# mcu.net
KiCad netlist of a schematic drawn in Altium Designer
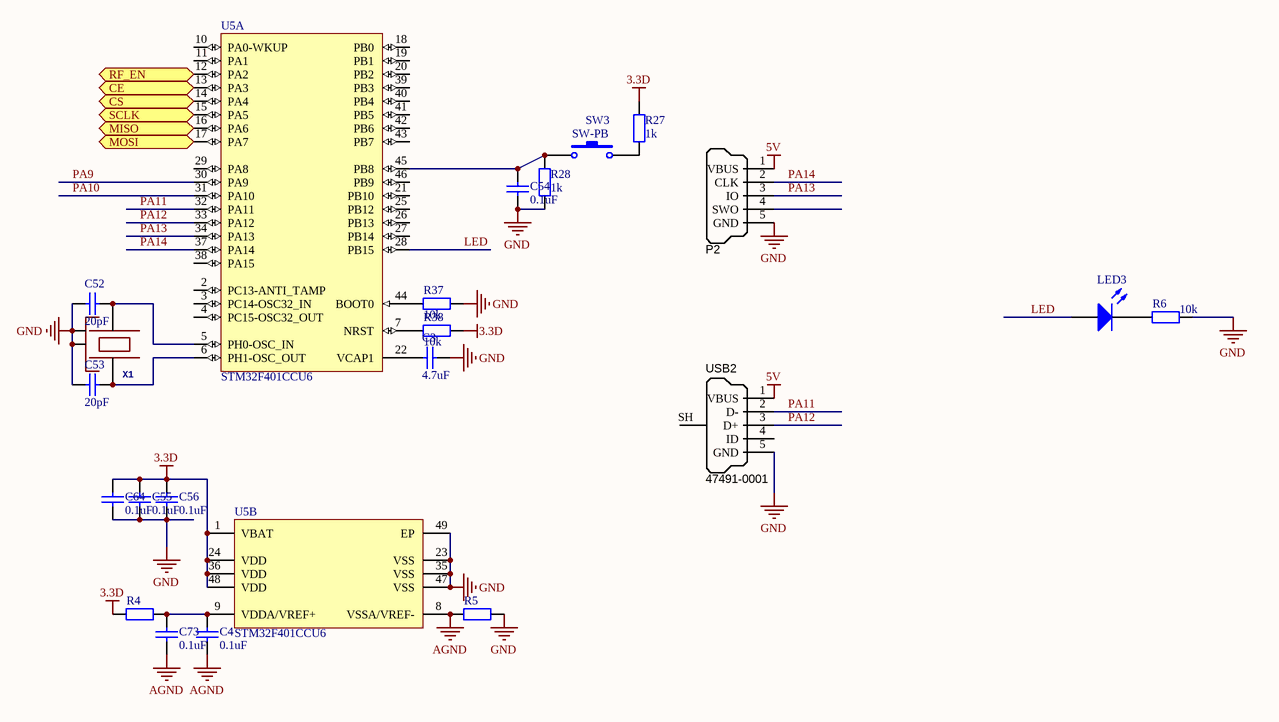
[diagram p0: mcu.SchDoc]

(export (version "E")
  (design (tool "Eeschema 10.0.6"))
  (components
    (comp (ref "C3")
      (value "4.7uF")
      (footprint "0603")
      (description "Capacitor")
      (fields (field (name "Comment") "Cap") (field (name "PUBLISHER") "Altium Limited"))
      (libsource (lib "RTC6705") (part "Cap"))
    )
    (comp (ref "C4")
      (value "0.1uF")
      (footprint "0402")
      (description "Capacitor")
      (fields (field (name "Comment") "Cap") (field (name "PUBLISHER") "Altium Limited"))
      (libsource (lib "RTC6705") (part "Cap"))
    )
    (comp (ref "C52")
      (value "20pF")
      (footprint "0402")
      (description "Capacitor")
      (fields (field (name "Comment") "Cap") (field (name "PUBLISHER") "Altium Limited"))
      (libsource (lib "RTC6705") (part "Cap"))
    )
    (comp (ref "C53")
      (value "20pF")
      (footprint "0402")
      (description "Capacitor")
      (fields (field (name "Comment") "Cap") (field (name "PUBLISHER") "Altium Limited"))
      (libsource (lib "RTC6705") (part "Cap"))
    )
    (comp (ref "C54")
      (value "0.1uF")
      (footprint "0402")
      (description "Capacitor")
      (fields (field (name "Comment") "Cap") (field (name "PUBLISHER") "Altium Limited"))
      (libsource (lib "RTC6705") (part "Cap"))
    )
    (comp (ref "C55")
      (value "0.1uF")
      (footprint "0402")
      (description "Capacitor")
      (fields (field (name "Comment") "Cap") (field (name "PUBLISHER") "Altium Limited"))
      (libsource (lib "RTC6705") (part "Cap"))
    )
    (comp (ref "C56")
      (value "0.1uF")
      (footprint "0402")
      (description "Capacitor")
      (fields (field (name "Comment") "Cap") (field (name "PUBLISHER") "Altium Limited"))
      (libsource (lib "RTC6705") (part "Cap"))
    )
    (comp (ref "C64")
      (value "0.1uF")
      (footprint "0402")
      (description "Capacitor")
      (fields (field (name "Comment") "Cap") (field (name "PUBLISHER") "Altium Limited"))
      (libsource (lib "RTC6705") (part "Cap"))
    )
    (comp (ref "C73")
      (value "0.1uF")
      (footprint "0402")
      (description "Capacitor")
      (fields (field (name "Comment") "Cap") (field (name "PUBLISHER") "Altium Limited"))
      (libsource (lib "RTC6705") (part "Cap"))
    )
    (comp (ref "LED3")
      (value "LED0")
      (footprint "0603")
      (description "Typical INFRARED GaAs LED")
      (fields (field (name "PUBLISHER") "Altium Limited"))
      (libsource (lib "Miscellaneous Devices") (part "LED0"))
    )
    (comp (ref "P2")
      (value "SWD_MicroUSB")
      (footprint "MICRO-YZX")
      (description "Connector SMD USB Micro Type B middle mount")
      (libsource (lib "sch") (part "SWD_MicroUSB"))
    )
    (comp (ref "R4")
      (value "0R/FB")
      (footprint "0402")
      (description "Resistor")
      (fields (field (name "PUBLISHER") "Altium Limited"))
      (libsource (lib "RTC6705") (part "Res2"))
    )
    (comp (ref "R5")
      (value "0R/FB")
      (footprint "0402")
      (description "Resistor")
      (fields (field (name "PUBLISHER") "Altium Limited"))
      (libsource (lib "RTC6705") (part "Res2"))
    )
    (comp (ref "R6")
      (value "10k")
      (footprint "0402")
      (description "Resistor")
      (fields (field (name "PUBLISHER") "Altium Limited"))
      (libsource (lib "Miscellaneous Devices") (part "Res2"))
    )
    (comp (ref "R27")
      (value "1k")
      (footprint "0402")
      (description "Resistor")
      (fields (field (name "PUBLISHER") "Altium Limited"))
      (libsource (lib "") (part "Res2_1"))
    )
    (comp (ref "R28")
      (value "1k")
      (footprint "0402")
      (description "Resistor")
      (fields (field (name "PUBLISHER") "Altium Limited"))
      (libsource (lib "") (part "Res2_1"))
    )
    (comp (ref "R37")
      (value "10k")
      (footprint "0402")
      (description "Resistor")
      (fields (field (name "Comment") "Res2") (field (name "PUBLISHER") "Altium Limited"))
      (libsource (lib "") (part "Res2_1"))
    )
    (comp (ref "R38")
      (value "10k")
      (footprint "0402")
      (description "Resistor")
      (fields (field (name "Comment") "Res2") (field (name "PUBLISHER") "Altium Limited"))
      (libsource (lib "RTC6705") (part "Res2"))
    )
    (comp (ref "SW3")
      (value "SW-PB")
      (footprint "SW3x4")
      (description "Switch")
      (fields (field (name "PUBLISHER") "Altium Limited"))
      (libsource (lib "Miscellaneous Devices") (part "SW-PB"))
    )
    (comp (ref "U5")
      (value "STM32F401CCU6")
      (footprint "STM-UFQFPN48_N")
      (fields (field (name "MANUFACTURER") "STMicroelectronics"))
      (libsource (lib "STMicroelectronics STM32 F4") (part "STM32F401CCU6"))
    )
    (comp (ref "USB2")
      (value "USB Micro Type B")
      (footprint "MICRO-YZX")
      (description "Connector SMD USB Micro Type B middle mount")
      (fields (field (name "MANUFACTURER PART NUMBER 1") "47491-0001"))
      (libsource (lib "PBL - Connectors") (part "USB_Micro_TypeB"))
    )
    (comp (ref "X1")
      (value "24.000 KHz 3.2x2.5mm 8-10pf")
      (footprint "OSCILLATOR-3.2X2.5")
      (description "Crystal Oscillator in 3.2x2.5 SMD")
      (libsource (lib "pixhawk2") (part "OSCILLATOR-3.2X2.5"))
    )
  )
  (nets
    (net (code "1") (name "/CE") (class "Default")
      (node (ref "U5") (pin "13") (pinfunction "PA3_13") (pintype "bidirectional"))
    )
    (net (code "2") (name "/CS") (class "Default")
      (node (ref "U5") (pin "14") (pinfunction "PA4_14") (pintype "bidirectional"))
    )
    (net (code "3") (name "/LED") (class "Default")
      (node (ref "LED3") (pin "1") (pinfunction "A_1") (pintype "passive"))
      (node (ref "U5") (pin "28") (pinfunction "PB15_28") (pintype "bidirectional"))
    )
    (net (code "4") (name "/MISO") (class "Default")
      (node (ref "U5") (pin "16") (pinfunction "PA6_16") (pintype "bidirectional"))
    )
    (net (code "5") (name "/MOSI") (class "Default")
      (node (ref "U5") (pin "17") (pinfunction "PA7_17") (pintype "bidirectional"))
    )
    (net (code "6") (name "/PA9") (class "Default")
      (node (ref "U5") (pin "30") (pinfunction "PA9_30") (pintype "bidirectional"))
    )
    (net (code "7") (name "/PA10") (class "Default")
      (node (ref "U5") (pin "31") (pinfunction "PA10_31") (pintype "bidirectional"))
    )
    (net (code "8") (name "/PA11") (class "Default")
      (node (ref "U5") (pin "32") (pinfunction "PA11_32") (pintype "bidirectional"))
      (node (ref "USB2") (pin "2") (pinfunction "D-_2") (pintype "passive"))
    )
    (net (code "9") (name "/PA12") (class "Default")
      (node (ref "U5") (pin "33") (pinfunction "PA12_33") (pintype "bidirectional"))
      (node (ref "USB2") (pin "3") (pinfunction "D+_3") (pintype "passive"))
    )
    (net (code "10") (name "/PA13") (class "Default")
      (node (ref "P2") (pin "3") (pinfunction "IO_3") (pintype "passive"))
      (node (ref "U5") (pin "34") (pinfunction "PA13_34") (pintype "bidirectional"))
    )
    (net (code "11") (name "/PA14") (class "Default")
      (node (ref "P2") (pin "2") (pinfunction "CLK_2") (pintype "passive"))
      (node (ref "U5") (pin "37") (pinfunction "PA14_37") (pintype "bidirectional"))
    )
    (net (code "12") (name "/RF_EN") (class "Default")
      (node (ref "U5") (pin "12") (pinfunction "PA2_12") (pintype "bidirectional"))
    )
    (net (code "13") (name "/SCLK") (class "Default")
      (node (ref "U5") (pin "15") (pinfunction "PA5_15") (pintype "bidirectional"))
    )
    (net (code "14") (name "3.3D") (class "Default")
      (node (ref "C55") (pin "2") (pinfunction "2_2") (pintype "passive"))
      (node (ref "C56") (pin "2") (pinfunction "2_2") (pintype "passive"))
      (node (ref "C64") (pin "2") (pinfunction "2_2") (pintype "passive"))
      (node (ref "R27") (pin "2") (pinfunction "2_2") (pintype "passive"))
      (node (ref "R38") (pin "1") (pinfunction "1_1") (pintype "passive"))
      (node (ref "R4") (pin "2") (pinfunction "2_2") (pintype "passive"))
      (node (ref "U5") (pin "1") (pinfunction "VBAT_1") (pintype "power_in"))
      (node (ref "U5") (pin "24") (pinfunction "VDD_24") (pintype "power_in"))
      (node (ref "U5") (pin "36") (pinfunction "VDD_36") (pintype "power_in"))
      (node (ref "U5") (pin "48") (pinfunction "VDD_48") (pintype "power_in"))
    )
    (net (code "15") (name "5V") (class "Default")
      (node (ref "P2") (pin "1") (pinfunction "VBUS_1") (pintype "passive"))
      (node (ref "USB2") (pin "1") (pinfunction "VBUS_1") (pintype "passive"))
    )
    (net (code "16") (name "AGND") (class "Default")
      (node (ref "C4") (pin "1") (pinfunction "1_1") (pintype "passive"))
      (node (ref "C73") (pin "1") (pinfunction "1_1") (pintype "passive"))
      (node (ref "R5") (pin "2") (pinfunction "2_2") (pintype "passive"))
      (node (ref "U5") (pin "8") (pinfunction "VSSA/VREF-_8") (pintype "power_in"))
    )
    (net (code "17") (name "GND") (class "Default")
      (node (ref "C3") (pin "1") (pinfunction "1_1") (pintype "passive"))
      (node (ref "C52") (pin "1") (pinfunction "1_1") (pintype "passive"))
      (node (ref "C53") (pin "1") (pinfunction "1_1") (pintype "passive"))
      (node (ref "C54") (pin "1") (pinfunction "1_1") (pintype "passive"))
      (node (ref "C55") (pin "1") (pinfunction "1_1") (pintype "passive"))
      (node (ref "C56") (pin "1") (pinfunction "1_1") (pintype "passive"))
      (node (ref "C64") (pin "1") (pinfunction "1_1") (pintype "passive"))
      (node (ref "P2") (pin "5") (pinfunction "GND_5") (pintype "passive"))
      (node (ref "R28") (pin "1") (pinfunction "1_1") (pintype "passive"))
      (node (ref "R37") (pin "2") (pinfunction "2_2") (pintype "passive"))
      (node (ref "R5") (pin "1") (pinfunction "1_1") (pintype "passive"))
      (node (ref "R6") (pin "2") (pinfunction "2_2") (pintype "passive"))
      (node (ref "U5") (pin "23") (pinfunction "VSS_23") (pintype "power_in"))
      (node (ref "U5") (pin "35") (pinfunction "VSS_35") (pintype "power_in"))
      (node (ref "U5") (pin "47") (pinfunction "VSS_47") (pintype "power_in"))
      (node (ref "U5") (pin "49") (pinfunction "EP_49") (pintype "power_in"))
      (node (ref "USB2") (pin "5") (pinfunction "GND_5") (pintype "passive"))
      (node (ref "X1") (pin "2") (pinfunction "NC_2_2") (pintype "open_emitter"))
      (node (ref "X1") (pin "4") (pinfunction "NC_4_4") (pintype "open_emitter"))
    )
    (net (code "18") (name "Net-(LED3-K)") (class "Default")
      (node (ref "LED3") (pin "2") (pinfunction "K_2") (pintype "passive"))
      (node (ref "R6") (pin "1") (pinfunction "1_1") (pintype "passive"))
    )
    (net (code "19") (name "Net-(R27-Pad1)") (class "Default")
      (node (ref "R27") (pin "1") (pinfunction "1_1") (pintype "passive"))
      (node (ref "SW3") (pin "2") (pinfunction "2_2") (pintype "passive"))
    )
    (net (code "20") (name "Net-(U5A-BOOT0)") (class "Default")
      (node (ref "R37") (pin "1") (pinfunction "1_1") (pintype "passive"))
      (node (ref "U5") (pin "44") (pinfunction "BOOT0_44") (pintype "input"))
    )
    (net (code "21") (name "Net-(U5A-NRST)") (class "Default")
      (node (ref "R38") (pin "2") (pinfunction "2_2") (pintype "passive"))
      (node (ref "U5") (pin "7") (pinfunction "NRST_7") (pintype "bidirectional"))
    )
    (net (code "22") (name "Net-(U5A-PB8)") (class "Default")
      (node (ref "C54") (pin "2") (pinfunction "2_2") (pintype "passive"))
      (node (ref "R28") (pin "2") (pinfunction "2_2") (pintype "passive"))
      (node (ref "SW3") (pin "1") (pinfunction "1_1") (pintype "passive"))
      (node (ref "U5") (pin "45") (pinfunction "PB8_45") (pintype "bidirectional"))
    )
    (net (code "23") (name "Net-(U5A-PH0-OSC_IN)") (class "Default")
      (node (ref "C52") (pin "2") (pinfunction "2_2") (pintype "passive"))
      (node (ref "U5") (pin "5") (pinfunction "PH0-OSC_IN_5") (pintype "bidirectional"))
      (node (ref "X1") (pin "1") (pinfunction "1_1") (pintype "passive"))
    )
    (net (code "24") (name "Net-(U5A-PH1-OSC_OUT)") (class "Default")
      (node (ref "C53") (pin "2") (pinfunction "2_2") (pintype "passive"))
      (node (ref "U5") (pin "6") (pinfunction "PH1-OSC_OUT_6") (pintype "bidirectional"))
      (node (ref "X1") (pin "3") (pinfunction "3_3") (pintype "passive"))
    )
    (net (code "25") (name "Net-(U5A-VCAP1)") (class "Default")
      (node (ref "C3") (pin "2") (pinfunction "2_2") (pintype "passive"))
      (node (ref "U5") (pin "22") (pinfunction "VCAP1_22") (pintype "power_in"))
    )
    (net (code "26") (name "Net-(U5B-VDDA{slash}VREF+)") (class "Default")
      (node (ref "C4") (pin "2") (pinfunction "2_2") (pintype "passive"))
      (node (ref "C73") (pin "2") (pinfunction "2_2") (pintype "passive"))
      (node (ref "R4") (pin "1") (pinfunction "1_1") (pintype "passive"))
      (node (ref "U5") (pin "9") (pinfunction "VDDA/VREF+_9") (pintype "power_in"))
    )
    (net (code "27") (name "unconnected-(P2-SWO-Pad4)") (class "Default")
      (node (ref "P2") (pin "4") (pinfunction "SWO_4") (pintype "passive"))
    )
    (net (code "28") (name "unconnected-(U5A-PA0-WKUP-Pad10)") (class "Default")
      (node (ref "U5") (pin "10") (pinfunction "PA0-WKUP_10") (pintype "bidirectional"))
    )
    (net (code "29") (name "unconnected-(U5A-PA1-Pad11)") (class "Default")
      (node (ref "U5") (pin "11") (pinfunction "PA1_11") (pintype "bidirectional"))
    )
    (net (code "30") (name "unconnected-(U5A-PA8-Pad29)") (class "Default")
      (node (ref "U5") (pin "29") (pinfunction "PA8_29") (pintype "bidirectional"))
    )
    (net (code "31") (name "unconnected-(U5A-PA15-Pad38)") (class "Default")
      (node (ref "U5") (pin "38") (pinfunction "PA15_38") (pintype "bidirectional"))
    )
    (net (code "32") (name "unconnected-(U5A-PB0-Pad18)") (class "Default")
      (node (ref "U5") (pin "18") (pinfunction "PB0_18") (pintype "bidirectional"))
    )
    (net (code "33") (name "unconnected-(U5A-PB1-Pad19)") (class "Default")
      (node (ref "U5") (pin "19") (pinfunction "PB1_19") (pintype "bidirectional"))
    )
    (net (code "34") (name "unconnected-(U5A-PB2-Pad20)") (class "Default")
      (node (ref "U5") (pin "20") (pinfunction "PB2_20") (pintype "bidirectional"))
    )
    (net (code "35") (name "unconnected-(U5A-PB3-Pad39)") (class "Default")
      (node (ref "U5") (pin "39") (pinfunction "PB3_39") (pintype "bidirectional"))
    )
    (net (code "36") (name "unconnected-(U5A-PB4-Pad40)") (class "Default")
      (node (ref "U5") (pin "40") (pinfunction "PB4_40") (pintype "bidirectional"))
    )
    (net (code "37") (name "unconnected-(U5A-PB5-Pad41)") (class "Default")
      (node (ref "U5") (pin "41") (pinfunction "PB5_41") (pintype "bidirectional"))
    )
    (net (code "38") (name "unconnected-(U5A-PB6-Pad42)") (class "Default")
      (node (ref "U5") (pin "42") (pinfunction "PB6_42") (pintype "bidirectional"))
    )
    (net (code "39") (name "unconnected-(U5A-PB7-Pad43)") (class "Default")
      (node (ref "U5") (pin "43") (pinfunction "PB7_43") (pintype "bidirectional"))
    )
    (net (code "40") (name "unconnected-(U5A-PB9-Pad46)") (class "Default")
      (node (ref "U5") (pin "46") (pinfunction "PB9_46") (pintype "bidirectional"))
    )
    (net (code "41") (name "unconnected-(U5A-PB10-Pad21)") (class "Default")
      (node (ref "U5") (pin "21") (pinfunction "PB10_21") (pintype "bidirectional"))
    )
    (net (code "42") (name "unconnected-(U5A-PB12-Pad25)") (class "Default")
      (node (ref "U5") (pin "25") (pinfunction "PB12_25") (pintype "bidirectional"))
    )
    (net (code "43") (name "unconnected-(U5A-PB13-Pad26)") (class "Default")
      (node (ref "U5") (pin "26") (pinfunction "PB13_26") (pintype "bidirectional"))
    )
    (net (code "44") (name "unconnected-(U5A-PB14-Pad27)") (class "Default")
      (node (ref "U5") (pin "27") (pinfunction "PB14_27") (pintype "bidirectional"))
    )
    (net (code "45") (name "unconnected-(U5A-PC13-ANTI_TAMP-Pad2)") (class "Default")
      (node (ref "U5") (pin "2") (pinfunction "PC13-ANTI_TAMP_2") (pintype "bidirectional"))
    )
    (net (code "46") (name "unconnected-(U5A-PC14-OSC32_IN-Pad3)") (class "Default")
      (node (ref "U5") (pin "3") (pinfunction "PC14-OSC32_IN_3") (pintype "bidirectional"))
    )
    (net (code "47") (name "unconnected-(U5A-PC15-OSC32_OUT-Pad4)") (class "Default")
      (node (ref "U5") (pin "4") (pinfunction "PC15-OSC32_OUT_4") (pintype "bidirectional"))
    )
    (net (code "48") (name "unconnected-(USB2-ID-Pad4)") (class "Default")
      (node (ref "USB2") (pin "4") (pinfunction "ID_4") (pintype "passive"))
    )
    (net (code "49") (name "unconnected-(USB2-Shell-PadSH)") (class "Default")
      (node (ref "USB2") (pin "SH") (pinfunction "Shell_SH") (pintype "passive"))
    )
  )
)
